# Boost_Converter.net
KiCad netlist of a schematic drawn in Altium Designer
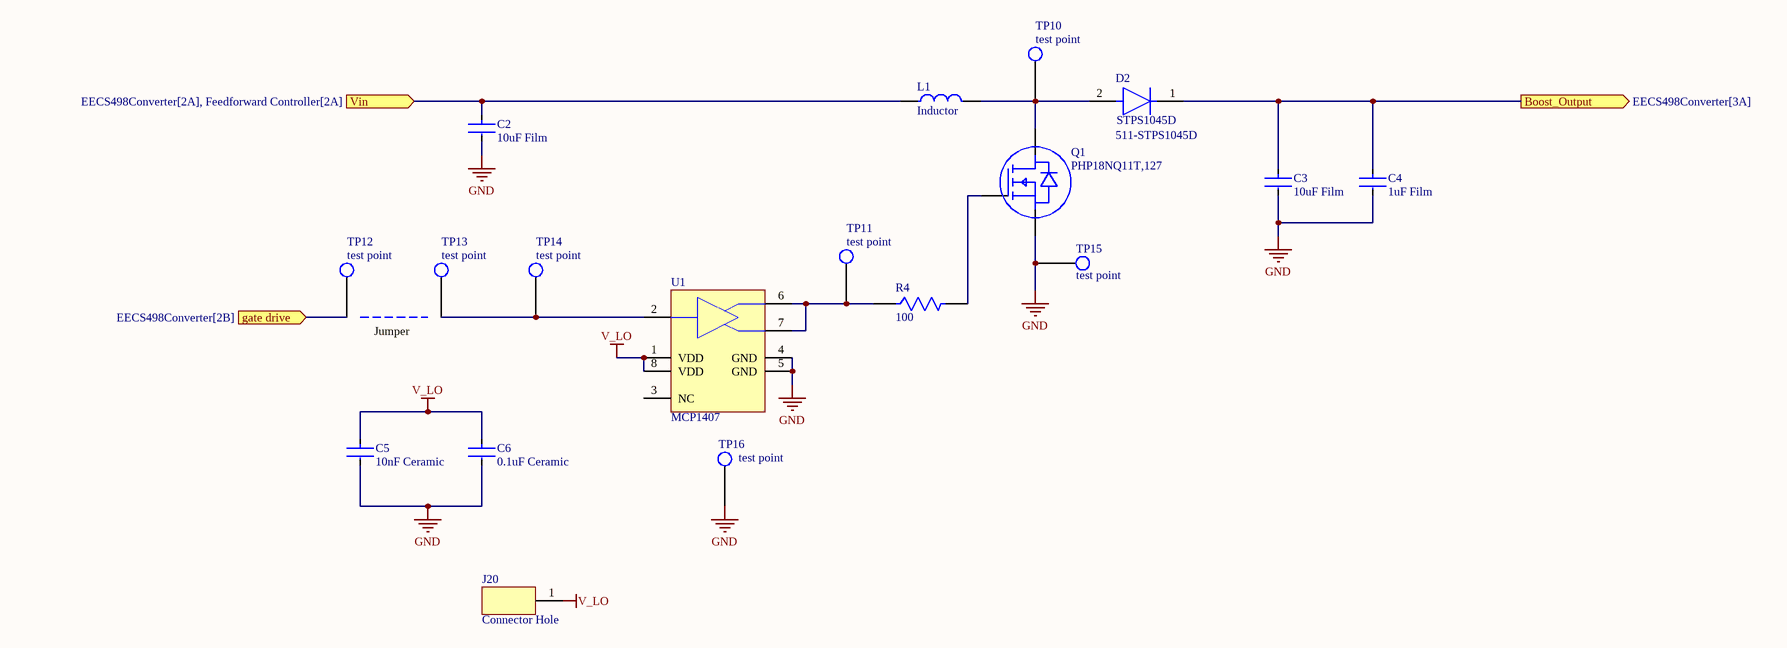
[diagram p0: Boost Converter.SchDoc]

(export (version "E")
  (design (tool "Eeschema 10.0.6"))
  (components
    (comp (ref "C2")
      (value "10uF Film")
      (footprint "FP-FILM-CAP-22.5mm")
      (description "CAP CER 10UF 50V X7R FILM")
      (fields (field (name "TOLERANCE") "10%") (field (name "VOLTAGE") "50V"))
      (libsource (lib "EECS498Converter") (part "10uF Capacitor"))
    )
    (comp (ref "C3")
      (value "10uF Film")
      (footprint "FP-FILM-CAP-22.5mm")
      (description "CAP CER 10UF 50V X7R FILM")
      (fields (field (name "TOLERANCE") "10%") (field (name "VOLTAGE") "50V"))
      (libsource (lib "EECS498Converter") (part "10uF Capacitor"))
    )
    (comp (ref "C4")
      (value "1uF Film")
      (footprint "FP-FILM-CAP-10mm")
      (description "CAP CER 1UF 50V X7R FILM")
      (fields (field (name "TOLERANCE") "10%") (field (name "VOLTAGE") "50V"))
      (libsource (lib "EECS498Converter") (part "1uf Capacitor"))
    )
    (comp (ref "C5")
      (value "10nF Ceramic")
      (footprint "FP-K15H5-MFG")
      (description "CAP CER 10nF 50V X7R RADIAL")
      (fields (field (name "TOLERANCE") "10%") (field (name "VOLTAGE") "50V"))
      (libsource (lib "EECS498Converter") (part "10nF Capacitor"))
    )
    (comp (ref "C6")
      (value "0.1uF Ceramic")
      (footprint "FP-K15H5-MFG")
      (description "CAP CER 0.1UF 50V X7R RADIAL")
      (fields (field (name "TOLERANCE") "10%") (field (name "VOLTAGE") "50V"))
      (libsource (lib "EECS498Converter") (part "0.1uF Capacitor"))
    )
    (comp (ref "D2")
      (value "STPS1045D")
      (footprint "STPS1045D")
      (description "Diode 45 V 10A Through Hole TO-220AC")
      (fields (field (name "SUPPLIER PART NUMBER 1") "511-STPS1045D"))
      (libsource (lib "EECS498Converter") (part "STPS1045D"))
    )
    (comp (ref "J20")
      (value "Connector Hole")
      (footprint "Connector Hole")
      (libsource (lib "EECS498Converter") (part "Connector Hole"))
    )
    (comp (ref "L1")
      (value "Inductor")
      (footprint "Power Inductor")
      (fields (field (name "TOLERANCE") "10%"))
      (libsource (lib "EECS498Converter") (part "Inductor"))
    )
    (comp (ref "Q1")
      (value "PHP18NQ11T,127")
      (footprint "1727-PHP18NQ11T,127-ND")
      (description "N-Channel 110 V 18A (Tc) 79W (Tc) Through Hole TO-220AB")
      (libsource (lib "EECS498Converter") (part "PHP18NQ11T,127"))
    )
    (comp (ref "R4")
      (value "100")
      (footprint "FP-RLR07-MFG")
      (description "Resistor, ± 1%, 250 mW, Axial Leaded, Metal Film, Military Reliability")
      (fields (field (name "TOLERANCE") "1%"))
      (libsource (lib "EECS498Converter") (part "Resistor"))
    )
    (comp (ref "TP10")
      (value "test point")
      (footprint "test point")
      (libsource (lib "EECS498Converter") (part "test point"))
    )
    (comp (ref "TP11")
      (value "test point")
      (footprint "test point")
      (libsource (lib "EECS498Converter") (part "test point"))
    )
    (comp (ref "TP12")
      (value "test point")
      (footprint "test point")
      (libsource (lib "EECS498Converter") (part "test point"))
    )
    (comp (ref "TP13")
      (value "test point")
      (footprint "test point")
      (libsource (lib "EECS498Converter") (part "test point"))
    )
    (comp (ref "TP14")
      (value "test point")
      (footprint "test point")
      (libsource (lib "EECS498Converter") (part "test point"))
    )
    (comp (ref "TP15")
      (value "test point")
      (footprint "test point")
      (libsource (lib "EECS498Converter") (part "test point"))
    )
    (comp (ref "TP16")
      (value "test point")
      (footprint "test point")
      (libsource (lib "EECS498Converter") (part "test point"))
    )
    (comp (ref "U1")
      (value "MCP1407")
      (footprint "DIP8")
      (description "6A High-Speed Power MOSFET Drivers, Non Inverting, Extended Temperature")
      (libsource (lib "EECS498Converter") (part "MCP1407"))
    )
  )
  (nets
    (net (code "1") (name "/Boost_Output") (class "Default")
      (node (ref "C3") (pin "1") (pinfunction "1_1") (pintype "passive"))
      (node (ref "C4") (pin "1") (pinfunction "1_1") (pintype "passive"))
      (node (ref "D2") (pin "1") (pinfunction "K_1") (pintype "passive"))
    )
    (net (code "2") (name "/Vin") (class "Default")
      (node (ref "C2") (pin "1") (pinfunction "1_1") (pintype "passive"))
      (node (ref "L1") (pin "1") (pinfunction "1_1") (pintype "passive"))
    )
    (net (code "3") (name "/gate drive") (class "Default") (node (ref "TP12") (pin "1") (pintype "passive")))
    (net (code "4") (name "GND") (class "Default")
      (node (ref "C2") (pin "2") (pinfunction "2_2") (pintype "passive"))
      (node (ref "C3") (pin "2") (pinfunction "2_2") (pintype "passive"))
      (node (ref "C4") (pin "2") (pinfunction "2_2") (pintype "passive"))
      (node (ref "C5") (pin "2") (pinfunction "2_2") (pintype "passive"))
      (node (ref "C6") (pin "2") (pinfunction "2_2") (pintype "passive"))
      (node (ref "Q1") (pin "3") (pinfunction "S_3") (pintype "passive"))
      (node (ref "TP15") (pin "1") (pintype "passive"))
      (node (ref "TP16") (pin "1") (pintype "passive"))
      (node (ref "U1") (pin "4") (pinfunction "GND_4") (pintype "power_in"))
      (node (ref "U1") (pin "5") (pinfunction "GND_5") (pintype "power_in"))
    )
    (net (code "5") (name "Net-(D2-A)") (class "Default")
      (node (ref "D2") (pin "2") (pinfunction "A_2") (pintype "passive"))
      (node (ref "L1") (pin "2") (pinfunction "2_2") (pintype "passive"))
      (node (ref "Q1") (pin "2") (pinfunction "D_2") (pintype "passive"))
      (node (ref "TP10") (pin "1") (pintype "passive"))
    )
    (net (code "6") (name "Net-(Q1-G)") (class "Default")
      (node (ref "Q1") (pin "1") (pinfunction "G_1") (pintype "passive"))
      (node (ref "R4") (pin "2") (pinfunction "2_2") (pintype "passive"))
    )
    (net (code "7") (name "Net-(R4-Pad1)") (class "Default")
      (node (ref "R4") (pin "1") (pinfunction "1_1") (pintype "passive"))
      (node (ref "TP11") (pin "1") (pintype "passive"))
      (node (ref "U1") (pin "6") (pinfunction "OUT_6") (pintype "passive"))
      (node (ref "U1") (pin "7") (pinfunction "OUT_7") (pintype "passive"))
    )
    (net (code "8") (name "Net-(U1-IN)") (class "Default")
      (node (ref "TP13") (pin "1") (pintype "passive"))
      (node (ref "TP14") (pin "1") (pintype "passive"))
      (node (ref "U1") (pin "2") (pinfunction "IN_2") (pintype "passive"))
    )
    (net (code "9") (name "V_LO") (class "Default")
      (node (ref "C5") (pin "1") (pinfunction "1_1") (pintype "passive"))
      (node (ref "C6") (pin "1") (pinfunction "1_1") (pintype "passive"))
      (node (ref "J20") (pin "1") (pinfunction "1_1") (pintype "passive"))
      (node (ref "U1") (pin "1") (pinfunction "VDD_1") (pintype "power_in"))
      (node (ref "U1") (pin "8") (pinfunction "VDD_8") (pintype "power_in"))
    )
    (net (code "10") (name "unconnected-(U1-NC-Pad3)") (class "Default")
      (node (ref "U1") (pin "3") (pinfunction "NC_3") (pintype "passive"))
    )
  )
)
